# CH32H417MEU6-UHSIF-Bottom-R0.net
KiCad netlist of a schematic drawn in Altium Designer
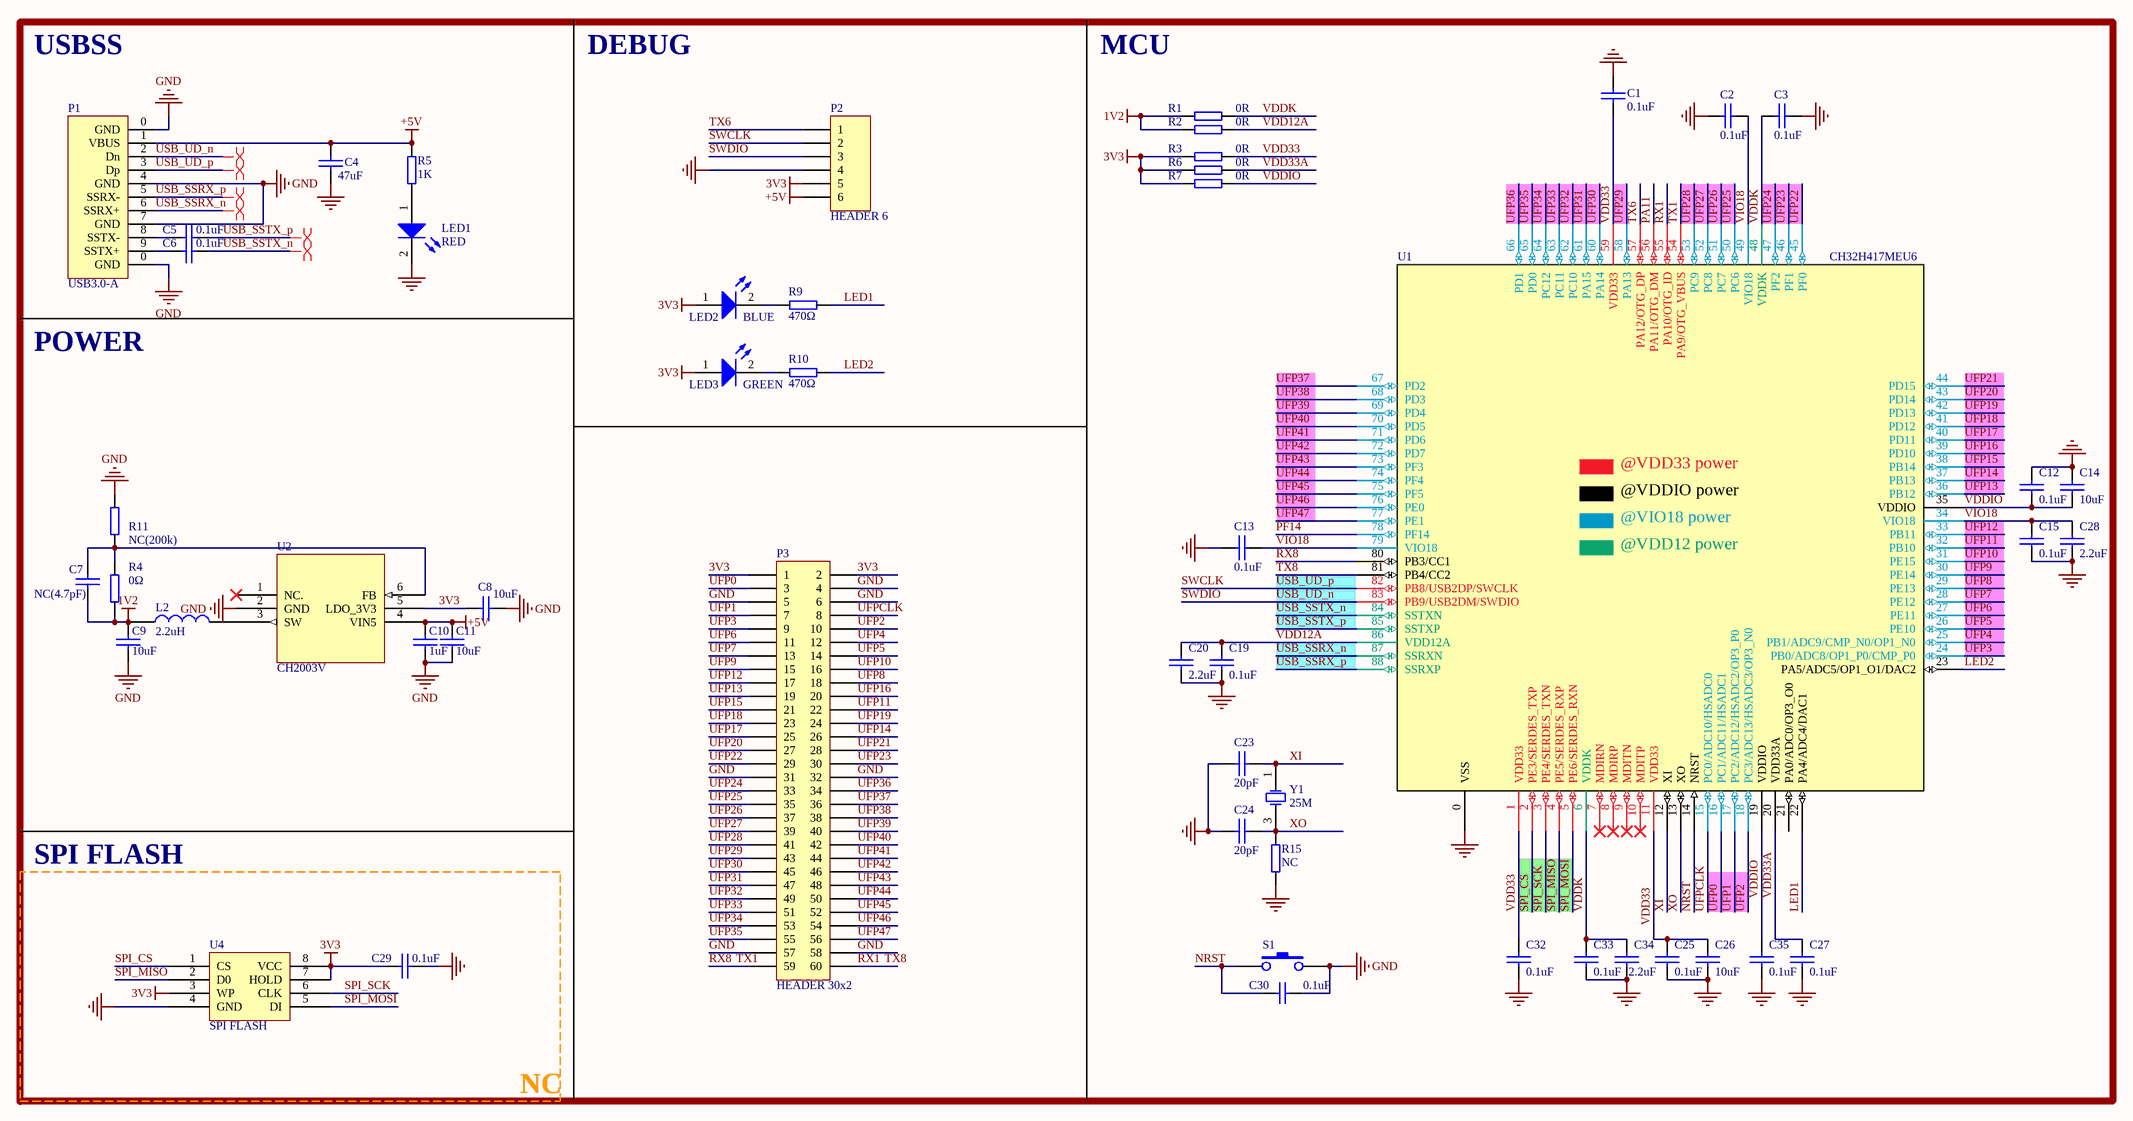
[diagram p0: CH32H417MEU6-UHSIF-Bottom-R0.SchDoc]

(export (version "E")
  (design (tool "Eeschema 10.0.6"))
  (components
    (comp (ref "C1")
      (value "0.1uF")
      (footprint "0402_C")
      (description "Capacitor")
      (libsource (lib "wch_sch_others") (part "CAP"))
    )
    (comp (ref "C2")
      (value "0.1uF")
      (footprint "0402_C")
      (description "Capacitor")
      (libsource (lib "wch_sch_others") (part "CAP"))
    )
    (comp (ref "C3")
      (value "0.1uF")
      (footprint "0402_C")
      (description "Capacitor")
      (libsource (lib "wch_sch_others") (part "CAP"))
    )
    (comp (ref "C4")
      (value "47uF")
      (footprint "3528_C")
      (description "Capacitor")
      (libsource (lib "wch_sch_others") (part "CAP"))
    )
    (comp (ref "C5")
      (value "0.1uF")
      (footprint "0402_C")
      (description "Capacitor")
      (libsource (lib "wch_sch_others") (part "CAP"))
    )
    (comp (ref "C6")
      (value "0.1uF")
      (footprint "0402_C")
      (description "Capacitor")
      (libsource (lib "wch_sch_others") (part "CAP"))
    )
    (comp (ref "C7")
      (value "NC(4.7pF)")
      (footprint "0402_C")
      (description "Capacitor")
      (libsource (lib "") (part "CAP_1"))
    )
    (comp (ref "C8")
      (value "10uF")
      (footprint "0603_C")
      (description "Capacitor")
      (libsource (lib "*") (part "CAP"))
    )
    (comp (ref "C9")
      (value "10uF")
      (footprint "0603_C")
      (description "Capacitor")
      (libsource (lib "*") (part "CAP"))
    )
    (comp (ref "C10")
      (value "1uF")
      (footprint "0402_C")
      (description "Capacitor")
      (libsource (lib "") (part "CAP_1"))
    )
    (comp (ref "C11")
      (value "10uF")
      (footprint "0603_C")
      (description "Capacitor")
      (libsource (lib "*") (part "CAP"))
    )
    (comp (ref "C12")
      (value "0.1uF")
      (footprint "0402_C")
      (description "Capacitor")
      (libsource (lib "wch_sch_others") (part "CAP"))
    )
    (comp (ref "C13")
      (value "0.1uF")
      (footprint "0402_C")
      (description "Capacitor")
      (libsource (lib "wch_sch_others") (part "CAP"))
    )
    (comp (ref "C14")
      (value "10uF")
      (footprint "0402_C")
      (description "Capacitor")
      (libsource (lib "wch_sch_others") (part "CAP"))
    )
    (comp (ref "C15")
      (value "0.1uF")
      (footprint "0402_C")
      (description "Capacitor")
      (libsource (lib "wch_sch_others") (part "CAP"))
    )
    (comp (ref "C19")
      (value "0.1uF")
      (footprint "0402_C")
      (description "Capacitor")
      (libsource (lib "wch_sch_others") (part "CAP"))
    )
    (comp (ref "C20")
      (value "2.2uF")
      (footprint "0402_C")
      (description "Capacitor")
      (libsource (lib "wch_sch_others") (part "CAP"))
    )
    (comp (ref "C23")
      (value "20pF")
      (footprint "0402_C")
      (description "Capacitor")
      (libsource (lib "wch_sch_others") (part "CAP"))
    )
    (comp (ref "C24")
      (value "20pF")
      (footprint "0402_C")
      (description "Capacitor")
      (libsource (lib "wch_sch_others") (part "CAP"))
    )
    (comp (ref "C25")
      (value "0.1uF")
      (footprint "0402_C")
      (description "Capacitor")
      (libsource (lib "wch_sch_others") (part "CAP"))
    )
    (comp (ref "C26")
      (value "10uF")
      (footprint "0402_C")
      (description "Capacitor")
      (libsource (lib "wch_sch_others") (part "CAP"))
    )
    (comp (ref "C27")
      (value "0.1uF")
      (footprint "0402_C")
      (description "Capacitor")
      (libsource (lib "wch_sch_others") (part "CAP"))
    )
    (comp (ref "C28")
      (value "2.2uF")
      (footprint "0402_C")
      (description "Capacitor")
      (libsource (lib "wch_sch_others") (part "CAP"))
    )
    (comp (ref "C29")
      (value "0.1uF")
      (footprint "0402_C")
      (description "Capacitor")
      (libsource (lib "wch_sch_others") (part "CAP"))
    )
    (comp (ref "C30")
      (value "0.1uF")
      (footprint "0402_C")
      (description "Capacitor")
      (libsource (lib "Miscellaneous Devices") (part "Cap"))
    )
    (comp (ref "C32")
      (value "0.1uF")
      (footprint "0402_C")
      (description "Capacitor")
      (libsource (lib "wch_sch_others") (part "CAP"))
    )
    (comp (ref "C33")
      (value "0.1uF")
      (footprint "0402_C")
      (description "Capacitor")
      (libsource (lib "wch_sch_others") (part "CAP"))
    )
    (comp (ref "C34")
      (value "2.2uF")
      (footprint "0402_C")
      (description "Capacitor")
      (libsource (lib "wch_sch_others") (part "CAP"))
    )
    (comp (ref "C35")
      (value "0.1uF")
      (footprint "0402_C")
      (description "Capacitor")
      (libsource (lib "wch_sch_others") (part "CAP"))
    )
    (comp (ref "L2") (value "2.2uH") (footprint "CD32") (libsource (lib "*") (part "INDUCTOR")))
    (comp (ref "LED1")
      (value "RED")
      (footprint "MYPCB:0603+")
      (description "Typical INFRARED GaAs LED")
      (libsource (lib "wch_sch_others") (part "LED"))
    )
    (comp (ref "LED2")
      (value "BLUE")
      (footprint "MYPCB:0603+")
      (description "Typical INFRARED GaAs LED")
      (libsource (lib "wch_sch_others") (part "LED"))
    )
    (comp (ref "LED3")
      (value "GREEN")
      (footprint "MYPCB:0603+")
      (description "Typical INFRARED GaAs LED")
      (libsource (lib "wch_sch_others") (part "LED"))
    )
    (comp (ref "P1")
      (value "USB3.0-A")
      (footprint "USB3.0-A-Receptacle")
      (libsource (lib "wch_sch_others") (part "USB3.0-A"))
    )
    (comp (ref "P2")
      (value "HEADER 6")
      (footprint "SIP6-2.54mm")
      (description "Header, 6-Pin")
      (libsource (lib "wch_sch_others") (part "HEADER 6"))
    )
    (comp (ref "P3")
      (value "HEADER 30x2")
      (footprint "MYPCB:BTB-60P-P0.5-MR")
      (description "Header, 30-Pin, Dual row")
      (libsource (lib "wch_sch_others") (part "HEADER 30x2"))
    )
    (comp (ref "R1") (value "0R") (footprint "0603") (libsource (lib "wch_sch_others") (part "RES")))
    (comp (ref "R2") (value "0R") (footprint "0603") (libsource (lib "wch_sch_others") (part "RES")))
    (comp (ref "R3") (value "0R") (footprint "0603") (libsource (lib "wch_sch_others") (part "RES")))
    (comp (ref "R4") (value "0Ω") (footprint "0402") (libsource (lib "wch_sch_others") (part "RES")))
    (comp (ref "R5") (value "1K") (footprint "0402") (libsource (lib "wch_sch_others") (part "RES")))
    (comp (ref "R6") (value "0R") (footprint "0603") (libsource (lib "wch_sch_others") (part "RES")))
    (comp (ref "R7") (value "0R") (footprint "0603") (libsource (lib "wch_sch_others") (part "RES")))
    (comp (ref "R9") (value "470Ω") (footprint "0402") (libsource (lib "wch_sch_others") (part "RES")))
    (comp (ref "R10") (value "470Ω") (footprint "0402") (libsource (lib "wch_sch_others") (part "RES")))
    (comp (ref "R11") (value "NC(200k)") (footprint "0402") (libsource (lib "wch_sch_others") (part "RES")))
    (comp (ref "R15") (value "NC") (footprint "0402") (libsource (lib "*") (part "RES")))
    (comp (ref "S1") (value "~") (footprint "贴片按键") (libsource (lib "wch_sch_others") (part "KEY1")))
    (comp (ref "U1")
      (value "CH32H417MEU6")
      (footprint "QFN88_10X10")
      (description "RISC-V FPU HD-MCU, 384MHz, USB3.0 & PD, 100M Ethernet, DVP, SDMMC, QSPI, OPA, ADC, DAC")
      (libsource (lib "DHXXXSCH") (part "CH32H417MEU6"))
    )
    (comp (ref "U2")
      (value "CH2003V")
      (footprint "SOT-23-6")
      (description "Step-Down DC-DC Converter, 5V input, FB 0.6V, 800mA output, with LDO 3.3V * 200mA")
      (libsource (lib "DHXXXSCH") (part "CH2003K"))
    )
    (comp (ref "U4")
      (value "SPI FLASH")
      (footprint "SOIC-8_208mil")
      (libsource (lib "wch_sch_others") (part "W25Q64"))
    )
    (comp (ref "Y1")
      (value "25M")
      (footprint "XT3225")
      (description "Crystal Oscillator")
      (fields (field (name "PUBLISHER") "Altium Limited"))
      (libsource (lib "Miscellaneous Devices") (part "XTAL"))
    )
  )
  (nets
    (net (code "1") (name "+5V") (class "Default")
      (node (ref "C10") (pin "2") (pinfunction "2_2") (pintype "passive"))
      (node (ref "C11") (pin "2") (pinfunction "2_2") (pintype "passive"))
      (node (ref "C4") (pin "1") (pinfunction "1_1") (pintype "passive"))
      (node (ref "P1") (pin "1") (pinfunction "VBUS_1") (pintype "passive"))
      (node (ref "P2") (pin "6") (pinfunction "6_6") (pintype "passive"))
      (node (ref "R5") (pin "2") (pintype "passive"))
      (node (ref "U2") (pin "4") (pinfunction "VIN5_4") (pintype "power_in"))
    )
    (net (code "2") (name "/LED1") (class "Default")
      (node (ref "R9") (pin "1") (pintype "passive"))
      (node (ref "U1") (pin "22") (pinfunction "PA4/ADC4/DAC1_22") (pintype "bidirectional"))
    )
    (net (code "3") (name "/LED2") (class "Default")
      (node (ref "R10") (pin "1") (pintype "passive"))
      (node (ref "U1") (pin "23") (pinfunction "PA5/ADC5/OP1_O1/DAC2_23") (pintype "bidirectional"))
    )
    (net (code "4") (name "/NRST") (class "Default")
      (node (ref "C30") (pin "2") (pinfunction "2_2") (pintype "passive"))
      (node (ref "S1") (pin "1") (pinfunction "1_1") (pintype "passive"))
      (node (ref "U1") (pin "14") (pinfunction "NRST_14") (pintype "input"))
    )
    (net (code "5") (name "/PA11") (class "Default")
      (node (ref "U1") (pin "56") (pinfunction "PA11/OTG_DM_56") (pintype "bidirectional"))
    )
    (net (code "6") (name "/PF14") (class "Default")
      (node (ref "U1") (pin "78") (pinfunction "PF14_78") (pintype "bidirectional"))
    )
    (net (code "7") (name "/RX1") (class "Default")
      (node (ref "P3") (pin "60") (pinfunction "60_60") (pintype "passive"))
      (node (ref "U1") (pin "55") (pinfunction "PA10/OTG_ID_55") (pintype "bidirectional"))
      (node (ref "U1") (pin "81") (pinfunction "PB4/CC2_81") (pintype "bidirectional"))
    )
    (net (code "8") (name "/RX8") (class "Default")
      (node (ref "P3") (pin "59") (pinfunction "59_59") (pintype "passive"))
      (node (ref "U1") (pin "54") (pinfunction "PA9/OTG_VBUS_54") (pintype "bidirectional"))
      (node (ref "U1") (pin "80") (pinfunction "PB3/CC1_80") (pintype "bidirectional"))
    )
    (net (code "9") (name "/SPI_CS") (class "Default")
      (node (ref "U1") (pin "2") (pinfunction "PE3/SERDES_TXP_2") (pintype "bidirectional"))
      (node (ref "U4") (pin "1") (pinfunction "CS_1") (pintype "passive"))
    )
    (net (code "10") (name "/SPI_MISO") (class "Default")
      (node (ref "U1") (pin "4") (pinfunction "PE5/SERDES_RXP_4") (pintype "bidirectional"))
      (node (ref "U4") (pin "2") (pinfunction "D0_2") (pintype "passive"))
    )
    (net (code "11") (name "/SPI_MOSI") (class "Default")
      (node (ref "U1") (pin "5") (pinfunction "PE6/SERDES_RXN_5") (pintype "bidirectional"))
      (node (ref "U4") (pin "5") (pinfunction "DI_5") (pintype "passive"))
    )
    (net (code "12") (name "/SPI_SCK") (class "Default")
      (node (ref "U1") (pin "3") (pinfunction "PE4/SERDES_TXN_3") (pintype "bidirectional"))
      (node (ref "U4") (pin "6") (pinfunction "CLK_6") (pintype "passive"))
    )
    (net (code "13") (name "/SWCLK") (class "Default")
      (node (ref "P1") (pin "3") (pinfunction "Dp_3") (pintype "passive"))
      (node (ref "P2") (pin "2") (pinfunction "2_2") (pintype "passive"))
      (node (ref "U1") (pin "82") (pinfunction "PB8/USB2DP/SWCLK_82") (pintype "bidirectional"))
    )
    (net (code "14") (name "/SWDIO") (class "Default")
      (node (ref "P1") (pin "2") (pinfunction "Dn_2") (pintype "passive"))
      (node (ref "P2") (pin "3") (pinfunction "3_3") (pintype "passive"))
      (node (ref "U1") (pin "83") (pinfunction "PB9/USB2DM/SWDIO_83") (pintype "bidirectional"))
    )
    (net (code "15") (name "/TX6") (class "Default")
      (node (ref "P2") (pin "1") (pinfunction "1_1") (pintype "passive"))
      (node (ref "U1") (pin "57") (pinfunction "PA12/OTG_DP_57") (pintype "bidirectional"))
    )
    (net (code "16") (name "/UFP0") (class "Default")
      (node (ref "P3") (pin "3") (pinfunction "3_3") (pintype "passive"))
      (node (ref "U1") (pin "16") (pinfunction "PC1/ADC11/HSADC1_16") (pintype "bidirectional"))
    )
    (net (code "17") (name "/UFP1") (class "Default")
      (node (ref "P3") (pin "7") (pinfunction "7_7") (pintype "passive"))
      (node (ref "U1") (pin "17") (pinfunction "PC2/ADC12/HSADC2/OP3_P0_17") (pintype "bidirectional"))
    )
    (net (code "18") (name "/UFP2") (class "Default")
      (node (ref "P3") (pin "10") (pinfunction "10_10") (pintype "passive"))
      (node (ref "U1") (pin "18") (pinfunction "PC3/ADC13/HSADC3/OP3_N0_18") (pintype "bidirectional"))
    )
    (net (code "19") (name "/UFP3") (class "Default")
      (node (ref "P3") (pin "9") (pinfunction "9_9") (pintype "passive"))
      (node (ref "U1") (pin "24") (pinfunction "PB0/ADC8/OP1_P0/CMP_P0_24") (pintype "bidirectional"))
    )
    (net (code "20") (name "/UFP4") (class "Default")
      (node (ref "P3") (pin "12") (pinfunction "12_12") (pintype "passive"))
      (node (ref "U1") (pin "25") (pinfunction "PB1/ADC9/CMP_N0/OP1_N0_25") (pintype "bidirectional"))
    )
    (net (code "21") (name "/UFP5") (class "Default")
      (node (ref "P3") (pin "14") (pinfunction "14_14") (pintype "passive"))
      (node (ref "U1") (pin "26") (pinfunction "PE10_26") (pintype "bidirectional"))
    )
    (net (code "22") (name "/UFP6") (class "Default")
      (node (ref "P3") (pin "11") (pinfunction "11_11") (pintype "passive"))
      (node (ref "U1") (pin "27") (pinfunction "PE11_27") (pintype "bidirectional"))
    )
    (net (code "23") (name "/UFP7") (class "Default")
      (node (ref "P3") (pin "13") (pinfunction "13_13") (pintype "passive"))
      (node (ref "U1") (pin "28") (pinfunction "PE12_28") (pintype "bidirectional"))
    )
    (net (code "24") (name "/UFP8") (class "Default")
      (node (ref "P3") (pin "18") (pinfunction "18_18") (pintype "passive"))
      (node (ref "U1") (pin "29") (pinfunction "PE13_29") (pintype "bidirectional"))
    )
    (net (code "25") (name "/UFP9") (class "Default")
      (node (ref "P3") (pin "15") (pinfunction "15_15") (pintype "passive"))
      (node (ref "U1") (pin "30") (pinfunction "PE14_30") (pintype "bidirectional"))
    )
    (net (code "26") (name "/UFP10") (class "Default")
      (node (ref "P3") (pin "16") (pinfunction "16_16") (pintype "passive"))
      (node (ref "U1") (pin "31") (pinfunction "PE15_31") (pintype "bidirectional"))
    )
    (net (code "27") (name "/UFP11") (class "Default")
      (node (ref "P3") (pin "22") (pinfunction "22_22") (pintype "passive"))
      (node (ref "U1") (pin "32") (pinfunction "PB10_32") (pintype "bidirectional"))
    )
    (net (code "28") (name "/UFP12") (class "Default")
      (node (ref "P3") (pin "17") (pinfunction "17_17") (pintype "passive"))
      (node (ref "U1") (pin "33") (pinfunction "PB11_33") (pintype "bidirectional"))
    )
    (net (code "29") (name "/UFP13") (class "Default")
      (node (ref "P3") (pin "19") (pinfunction "19_19") (pintype "passive"))
      (node (ref "U1") (pin "36") (pinfunction "PB12_36") (pintype "bidirectional"))
    )
    (net (code "30") (name "/UFP14") (class "Default")
      (node (ref "P3") (pin "26") (pinfunction "26_26") (pintype "passive"))
      (node (ref "U1") (pin "37") (pinfunction "PB13_37") (pintype "bidirectional"))
    )
    (net (code "31") (name "/UFP15") (class "Default")
      (node (ref "P3") (pin "21") (pinfunction "21_21") (pintype "passive"))
      (node (ref "U1") (pin "38") (pinfunction "PB14_38") (pintype "bidirectional"))
    )
    (net (code "32") (name "/UFP16") (class "Default")
      (node (ref "P3") (pin "20") (pinfunction "20_20") (pintype "passive"))
      (node (ref "U1") (pin "39") (pinfunction "PD10_39") (pintype "bidirectional"))
    )
    (net (code "33") (name "/UFP17") (class "Default")
      (node (ref "P3") (pin "25") (pinfunction "25_25") (pintype "passive"))
      (node (ref "U1") (pin "40") (pinfunction "PD11_40") (pintype "bidirectional"))
    )
    (net (code "34") (name "/UFP18") (class "Default")
      (node (ref "P3") (pin "23") (pinfunction "23_23") (pintype "passive"))
      (node (ref "U1") (pin "41") (pinfunction "PD12_41") (pintype "bidirectional"))
    )
    (net (code "35") (name "/UFP19") (class "Default")
      (node (ref "P3") (pin "24") (pinfunction "24_24") (pintype "passive"))
      (node (ref "U1") (pin "42") (pinfunction "PD13_42") (pintype "bidirectional"))
    )
    (net (code "36") (name "/UFP20") (class "Default")
      (node (ref "P3") (pin "27") (pinfunction "27_27") (pintype "passive"))
      (node (ref "U1") (pin "43") (pinfunction "PD14_43") (pintype "bidirectional"))
    )
    (net (code "37") (name "/UFP21") (class "Default")
      (node (ref "P3") (pin "28") (pinfunction "28_28") (pintype "passive"))
      (node (ref "U1") (pin "44") (pinfunction "PD15_44") (pintype "bidirectional"))
    )
    (net (code "38") (name "/UFP22") (class "Default")
      (node (ref "P3") (pin "29") (pinfunction "29_29") (pintype "passive"))
      (node (ref "U1") (pin "45") (pinfunction "PF0_45") (pintype "bidirectional"))
    )
    (net (code "39") (name "/UFP23") (class "Default")
      (node (ref "P3") (pin "30") (pinfunction "30_30") (pintype "passive"))
      (node (ref "U1") (pin "46") (pinfunction "PF1_46") (pintype "bidirectional"))
    )
    (net (code "40") (name "/UFP24") (class "Default")
      (node (ref "P3") (pin "33") (pinfunction "33_33") (pintype "passive"))
      (node (ref "U1") (pin "47") (pinfunction "PF2_47") (pintype "bidirectional"))
    )
    (net (code "41") (name "/UFP25") (class "Default")
      (node (ref "P3") (pin "35") (pinfunction "35_35") (pintype "passive"))
      (node (ref "U1") (pin "50") (pinfunction "PC6_50") (pintype "bidirectional"))
    )
    (net (code "42") (name "/UFP26") (class "Default")
      (node (ref "P3") (pin "37") (pinfunction "37_37") (pintype "passive"))
      (node (ref "U1") (pin "51") (pinfunction "PC7_51") (pintype "bidirectional"))
    )
    (net (code "43") (name "/UFP27") (class "Default")
      (node (ref "P3") (pin "39") (pinfunction "39_39") (pintype "passive"))
      (node (ref "U1") (pin "52") (pinfunction "PC8_52") (pintype "bidirectional"))
    )
    (net (code "44") (name "/UFP28") (class "Default")
      (node (ref "P3") (pin "41") (pinfunction "41_41") (pintype "passive"))
      (node (ref "U1") (pin "53") (pinfunction "PC9_53") (pintype "bidirectional"))
    )
    (net (code "45") (name "/UFP29") (class "Default")
      (node (ref "P3") (pin "43") (pinfunction "43_43") (pintype "passive"))
      (node (ref "U1") (pin "58") (pinfunction "PA13_58") (pintype "bidirectional"))
    )
    (net (code "46") (name "/UFP30") (class "Default")
      (node (ref "P3") (pin "45") (pinfunction "45_45") (pintype "passive"))
      (node (ref "U1") (pin "60") (pinfunction "PA14_60") (pintype "bidirectional"))
    )
    (net (code "47") (name "/UFP31") (class "Default")
      (node (ref "P3") (pin "47") (pinfunction "47_47") (pintype "passive"))
      (node (ref "U1") (pin "61") (pinfunction "PA15_61") (pintype "bidirectional"))
    )
    (net (code "48") (name "/UFP32") (class "Default")
      (node (ref "P3") (pin "49") (pinfunction "49_49") (pintype "passive"))
      (node (ref "U1") (pin "62") (pinfunction "PC10_62") (pintype "bidirectional"))
    )
    (net (code "49") (name "/UFP33") (class "Default")
      (node (ref "P3") (pin "51") (pinfunction "51_51") (pintype "passive"))
      (node (ref "U1") (pin "63") (pinfunction "PC11_63") (pintype "bidirectional"))
    )
    (net (code "50") (name "/UFP34") (class "Default")
      (node (ref "P3") (pin "53") (pinfunction "53_53") (pintype "passive"))
      (node (ref "U1") (pin "64") (pinfunction "PC12_64") (pintype "bidirectional"))
    )
    (net (code "51") (name "/UFP35") (class "Default")
      (node (ref "P3") (pin "55") (pinfunction "55_55") (pintype "passive"))
      (node (ref "U1") (pin "65") (pinfunction "PD0_65") (pintype "bidirectional"))
    )
    (net (code "52") (name "/UFP36") (class "Default")
      (node (ref "P3") (pin "34") (pinfunction "34_34") (pintype "passive"))
      (node (ref "U1") (pin "66") (pinfunction "PD1_66") (pintype "bidirectional"))
    )
    (net (code "53") (name "/UFP37") (class "Default")
      (node (ref "P3") (pin "36") (pinfunction "36_36") (pintype "passive"))
      (node (ref "U1") (pin "67") (pinfunction "PD2_67") (pintype "bidirectional"))
    )
    (net (code "54") (name "/UFP38") (class "Default")
      (node (ref "P3") (pin "38") (pinfunction "38_38") (pintype "passive"))
      (node (ref "U1") (pin "68") (pinfunction "PD3_68") (pintype "bidirectional"))
    )
    (net (code "55") (name "/UFP39") (class "Default")
      (node (ref "P3") (pin "40") (pinfunction "40_40") (pintype "passive"))
      (node (ref "U1") (pin "69") (pinfunction "PD4_69") (pintype "bidirectional"))
    )
    (net (code "56") (name "/UFP40") (class "Default")
      (node (ref "P3") (pin "42") (pinfunction "42_42") (pintype "passive"))
      (node (ref "U1") (pin "70") (pinfunction "PD5_70") (pintype "bidirectional"))
    )
    (net (code "57") (name "/UFP41") (class "Default")
      (node (ref "P3") (pin "44") (pinfunction "44_44") (pintype "passive"))
      (node (ref "U1") (pin "71") (pinfunction "PD6_71") (pintype "bidirectional"))
    )
    (net (code "58") (name "/UFP42") (class "Default")
      (node (ref "P3") (pin "46") (pinfunction "46_46") (pintype "passive"))
      (node (ref "U1") (pin "72") (pinfunction "PD7_72") (pintype "bidirectional"))
    )
    (net (code "59") (name "/UFP43") (class "Default")
      (node (ref "P3") (pin "48") (pinfunction "48_48") (pintype "passive"))
      (node (ref "U1") (pin "73") (pinfunction "PF3_73") (pintype "bidirectional"))
    )
    (net (code "60") (name "/UFP44") (class "Default")
      (node (ref "P3") (pin "50") (pinfunction "50_50") (pintype "passive"))
      (node (ref "U1") (pin "74") (pinfunction "PF4_74") (pintype "bidirectional"))
    )
    (net (code "61") (name "/UFP45") (class "Default")
      (node (ref "P3") (pin "52") (pinfunction "52_52") (pintype "passive"))
      (node (ref "U1") (pin "75") (pinfunction "PF5_75") (pintype "bidirectional"))
    )
    (net (code "62") (name "/UFP46") (class "Default")
      (node (ref "P3") (pin "54") (pinfunction "54_54") (pintype "passive"))
      (node (ref "U1") (pin "76") (pinfunction "PE0_76") (pintype "bidirectional"))
    )
    (net (code "63") (name "/UFP47") (class "Default")
      (node (ref "P3") (pin "56") (pinfunction "56_56") (pintype "passive"))
      (node (ref "U1") (pin "77") (pinfunction "PE1_77") (pintype "bidirectional"))
    )
    (net (code "64") (name "/UFPCLK") (class "Default")
      (node (ref "P3") (pin "8") (pinfunction "8_8") (pintype "passive"))
      (node (ref "U1") (pin "15") (pinfunction "PC0/ADC10/HSADC0_15") (pintype "bidirectional"))
    )
    (net (code "65") (name "/USB_SSRX_n") (class "Default")
      (node (ref "P1") (pin "6") (pinfunction "SSRX+_6") (pintype "passive"))
      (node (ref "U1") (pin "87") (pinfunction "SSRXN_87") (pintype "bidirectional"))
    )
    (net (code "66") (name "/USB_SSRX_p") (class "Default")
      (node (ref "P1") (pin "5") (pinfunction "SSRX-_5") (pintype "passive"))
      (node (ref "U1") (pin "88") (pinfunction "SSRXP_88") (pintype "bidirectional"))
    )
    (net (code "67") (name "/USB_SSTX_n") (class "Default")
      (node (ref "C6") (pin "1") (pinfunction "1_1") (pintype "passive"))
      (node (ref "U1") (pin "84") (pinfunction "SSTXN_84") (pintype "bidirectional"))
    )
    (net (code "68") (name "/USB_SSTX_p") (class "Default")
      (node (ref "C5") (pin "1") (pinfunction "1_1") (pintype "passive"))
      (node (ref "U1") (pin "85") (pinfunction "SSTXP_85") (pintype "bidirectional"))
    )
    (net (code "69") (name "/VDD12A") (class "Default")
      (node (ref "C19") (pin "2") (pinfunction "2_2") (pintype "passive"))
      (node (ref "C20") (pin "2") (pinfunction "2_2") (pintype "passive"))
      (node (ref "R2") (pin "1") (pintype "passive"))
      (node (ref "U1") (pin "86") (pinfunction "VDD12A_86") (pintype "power_in"))
    )
    (net (code "70") (name "/VDD33") (class "Default")
      (node (ref "C1") (pin "1") (pinfunction "1_1") (pintype "passive"))
      (node (ref "C25") (pin "2") (pinfunction "2_2") (pintype "passive"))
      (node (ref "C26") (pin "2") (pinfunction "2_2") (pintype "passive"))
      (node (ref "C32") (pin "2") (pinfunction "2_2") (pintype "passive"))
      (node (ref "R3") (pin "1") (pintype "passive"))
      (node (ref "U1") (pin "1") (pinfunction "VDD33_1") (pintype "power_in"))
      (node (ref "U1") (pin "11") (pinfunction "VDD33_11") (pintype "power_in"))
      (node (ref "U1") (pin "59") (pinfunction "VDD33_59") (pintype "power_in"))
    )
    (net (code "71") (name "/VDD33A") (class "Default")
      (node (ref "C27") (pin "2") (pinfunction "2_2") (pintype "passive"))
      (node (ref "R6") (pin "1") (pintype "passive"))
      (node (ref "U1") (pin "20") (pinfunction "VDD33A_20") (pintype "power_in"))
    )
    (net (code "72") (name "/VDDIO") (class "Default")
      (node (ref "C12") (pin "1") (pinfunction "1_1") (pintype "passive"))
      (node (ref "C14") (pin "1") (pinfunction "1_1") (pintype "passive"))
      (node (ref "C35") (pin "2") (pinfunction "2_2") (pintype "passive"))
      (node (ref "R7") (pin "1") (pintype "passive"))
      (node (ref "U1") (pin "19") (pinfunction "VDDIO_19") (pintype "power_in"))
      (node (ref "U1") (pin "35") (pinfunction "VDDIO_35") (pintype "power_in"))
    )
    (net (code "73") (name "/VDDK") (class "Default")
      (node (ref "C3") (pin "2") (pinfunction "2_2") (pintype "passive"))
      (node (ref "C33") (pin "2") (pinfunction "2_2") (pintype "passive"))
      (node (ref "C34") (pin "2") (pinfunction "2_2") (pintype "passive"))
      (node (ref "R1") (pin "1") (pintype "passive"))
      (node (ref "U1") (pin "48") (pinfunction "VDDK_48") (pintype "power_in"))
      (node (ref "U1") (pin "6") (pinfunction "VDDK_6") (pintype "power_in"))
    )
    (net (code "74") (name "/VIO18") (class "Default")
      (node (ref "C13") (pin "1") (pinfunction "1_1") (pintype "passive"))
      (node (ref "C15") (pin "2") (pinfunction "2_2") (pintype "passive"))
      (node (ref "C2") (pin "1") (pinfunction "1_1") (pintype "passive"))
      (node (ref "C28") (pin "2") (pinfunction "2_2") (pintype "passive"))
      (node (ref "U1") (pin "34") (pinfunction "VIO18_34") (pintype "power_in"))
      (node (ref "U1") (pin "49") (pinfunction "VIO18_49") (pintype "power_in"))
      (node (ref "U1") (pin "79") (pinfunction "VIO18_79") (pintype "power_in"))
    )
    (net (code "75") (name "/XI") (class "Default")
      (node (ref "C23") (pin "2") (pinfunction "2_2") (pintype "passive"))
      (node (ref "U1") (pin "12") (pinfunction "XI_12") (pintype "bidirectional"))
      (node (ref "Y1") (pin "1") (pinfunction "OSC1_1") (pintype "passive"))
    )
    (net (code "76") (name "/XO") (class "Default")
      (node (ref "C24") (pin "2") (pinfunction "2_2") (pintype "passive"))
      (node (ref "R15") (pin "2") (pintype "passive"))
      (node (ref "U1") (pin "13") (pinfunction "XO_13") (pintype "bidirectional"))
      (node (ref "Y1") (pin "3") (pinfunction "OSC2_3") (pintype "passive"))
    )
    (net (code "77") (name "1V2") (class "Default")
      (node (ref "C7") (pin "1") (pinfunction "1_1") (pintype "passive"))
      (node (ref "C9") (pin "2") (pinfunction "2_2") (pintype "passive"))
      (node (ref "L2") (pin "2") (pinfunction "2_2") (pintype "passive"))
      (node (ref "R1") (pin "2") (pintype "passive"))
      (node (ref "R2") (pin "2") (pintype "passive"))
      (node (ref "R4") (pin "1") (pintype "passive"))
    )
    (net (code "78") (name "3V3") (class "Default")
      (node (ref "C29") (pin "2") (pinfunction "2_2") (pintype "passive"))
      (node (ref "C8") (pin "2") (pinfunction "2_2") (pintype "passive"))
      (node (ref "LED2") (pin "1") (pinfunction "A_1") (pintype "passive"))
      (node (ref "LED3") (pin "1") (pinfunction "A_1") (pintype "passive"))
      (node (ref "P2") (pin "5") (pinfunction "5_5") (pintype "passive"))
      (node (ref "P3") (pin "1") (pinfunction "1_1") (pintype "passive"))
      (node (ref "P3") (pin "2") (pinfunction "2_2") (pintype "passive"))
      (node (ref "R3") (pin "2") (pintype "passive"))
      (node (ref "R6") (pin "2") (pintype "passive"))
      (node (ref "R7") (pin "2") (pintype "passive"))
      (node (ref "U2") (pin "5") (pinfunction "LDO_3V3_5") (pintype "power_in"))
      (node (ref "U4") (pin "3") (pinfunction "WP_3") (pintype "passive"))
      (node (ref "U4") (pin "7") (pinfunction "HOLD_7") (pintype "passive"))
      (node (ref "U4") (pin "8") (pinfunction "VCC_8") (pintype "passive"))
    )
    (net (code "79") (name "GND") (class "Default")
      (node (ref "C1") (pin "2") (pinfunction "2_2") (pintype "passive"))
      (node (ref "C10") (pin "1") (pinfunction "1_1") (pintype "passive"))
      (node (ref "C11") (pin "1") (pinfunction "1_1") (pintype "passive"))
      (node (ref "C12") (pin "2") (pinfunction "2_2") (pintype "passive"))
      (node (ref "C13") (pin "2") (pinfunction "2_2") (pintype "passive"))
      (node (ref "C14") (pin "2") (pinfunction "2_2") (pintype "passive"))
      (node (ref "C15") (pin "1") (pinfunction "1_1") (pintype "passive"))
      (node (ref "C19") (pin "1") (pinfunction "1_1") (pintype "passive"))
      (node (ref "C2") (pin "2") (pinfunction "2_2") (pintype "passive"))
      (node (ref "C20") (pin "1") (pinfunction "1_1") (pintype "passive"))
      (node (ref "C23") (pin "1") (pinfunction "1_1") (pintype "passive"))
      (node (ref "C24") (pin "1") (pinfunction "1_1") (pintype "passive"))
      (node (ref "C25") (pin "1") (pinfunction "1_1") (pintype "passive"))
      (node (ref "C26") (pin "1") (pinfunction "1_1") (pintype "passive"))
      (node (ref "C27") (pin "1") (pinfunction "1_1") (pintype "passive"))
      (node (ref "C28") (pin "1") (pinfunction "1_1") (pintype "passive"))
      (node (ref "C29") (pin "1") (pinfunction "1_1") (pintype "passive"))
      (node (ref "C3") (pin "1") (pinfunction "1_1") (pintype "passive"))
      (node (ref "C30") (pin "1") (pinfunction "1_1") (pintype "passive"))
      (node (ref "C32") (pin "1") (pinfunction "1_1") (pintype "passive"))
      (node (ref "C33") (pin "1") (pinfunction "1_1") (pintype "passive"))
      (node (ref "C34") (pin "1") (pinfunction "1_1") (pintype "passive"))
      (node (ref "C35") (pin "1") (pinfunction "1_1") (pintype "passive"))
      (node (ref "C4") (pin "2") (pinfunction "2_2") (pintype "passive"))
      (node (ref "C8") (pin "1") (pinfunction "1_1") (pintype "passive"))
      (node (ref "C9") (pin "1") (pinfunction "1_1") (pintype "passive"))
      (node (ref "LED1") (pin "2") (pinfunction "K_2") (pintype "passive"))
      (node (ref "P1") (pin "0") (pinfunction "GND_0") (pintype "passive"))
      (node (ref "P1") (pin "4") (pinfunction "GND_4") (pintype "passive"))
      (node (ref "P1") (pin "7") (pinfunction "GND_7") (pintype "passive"))
      (node (ref "P2") (pin "4") (pinfunction "4_4") (pintype "passive"))
      (node (ref "P3") (pin "31") (pinfunction "31_31") (pintype "passive"))
      (node (ref "P3") (pin "32") (pinfunction "32_32") (pintype "passive"))
      (node (ref "P3") (pin "4") (pinfunction "4_4") (pintype "passive"))
      (node (ref "P3") (pin "5") (pinfunction "5_5") (pintype "passive"))
      (node (ref "P3") (pin "57") (pinfunction "57_57") (pintype "passive"))
      (node (ref "P3") (pin "58") (pinfunction "58_58") (pintype "passive"))
      (node (ref "P3") (pin "6") (pinfunction "6_6") (pintype "passive"))
      (node (ref "R11") (pin "2") (pintype "passive"))
      (node (ref "R15") (pin "1") (pintype "passive"))
      (node (ref "S1") (pin "2") (pinfunction "2_2") (pintype "passive"))
      (node (ref "U1") (pin "0") (pinfunction "VSS_0") (pintype "power_in"))
      (node (ref "U2") (pin "2") (pinfunction "GND_2") (pintype "power_in"))
      (node (ref "U4") (pin "4") (pinfunction "GND_4") (pintype "passive"))
    )
    (net (code "80") (name "Net-(LED1-A)") (class "Default")
      (node (ref "LED1") (pin "1") (pinfunction "A_1") (pintype "passive"))
      (node (ref "R5") (pin "1") (pintype "passive"))
    )
    (net (code "81") (name "Net-(LED2-K)") (class "Default")
      (node (ref "LED2") (pin "2") (pinfunction "K_2") (pintype "passive"))
      (node (ref "R9") (pin "2") (pintype "passive"))
    )
    (net (code "82") (name "Net-(LED3-K)") (class "Default")
      (node (ref "LED3") (pin "2") (pinfunction "K_2") (pintype "passive"))
      (node (ref "R10") (pin "2") (pintype "passive"))
    )
    (net (code "83") (name "Net-(P1-SSTX+)") (class "Default")
      (node (ref "C6") (pin "2") (pinfunction "2_2") (pintype "passive"))
      (node (ref "P1") (pin "9") (pinfunction "SSTX+_9") (pintype "passive"))
    )
    (net (code "84") (name "Net-(P1-SSTX-)") (class "Default")
      (node (ref "C5") (pin "2") (pinfunction "2_2") (pintype "passive"))
      (node (ref "P1") (pin "8") (pinfunction "SSTX-_8") (pintype "passive"))
    )
    (net (code "85") (name "Net-(U2-FB)") (class "Default")
      (node (ref "C7") (pin "2") (pinfunction "2_2") (pintype "passive"))
      (node (ref "R11") (pin "1") (pintype "passive"))
      (node (ref "R4") (pin "2") (pintype "passive"))
      (node (ref "U2") (pin "6") (pinfunction "FB_6") (pintype "input"))
    )
    (net (code "86") (name "Net-(U2-SW)") (class "Default")
      (node (ref "L2") (pin "1") (pinfunction "1_1") (pintype "passive"))
      (node (ref "U2") (pin "3") (pinfunction "SW_3") (pintype "output"))
    )
    (net (code "87") (name "unconnected-(U1-MDIRN-Pad7)") (class "Default")
      (node (ref "U1") (pin "7") (pinfunction "MDIRN_7") (pintype "bidirectional+no_connect"))
    )
    (net (code "88") (name "unconnected-(U1-MDIRP-Pad8)") (class "Default")
      (node (ref "U1") (pin "8") (pinfunction "MDIRP_8") (pintype "bidirectional+no_connect"))
    )
    (net (code "89") (name "unconnected-(U1-MDITN-Pad9)") (class "Default")
      (node (ref "U1") (pin "9") (pinfunction "MDITN_9") (pintype "bidirectional+no_connect"))
    )
    (net (code "90") (name "unconnected-(U1-MDITP-Pad10)") (class "Default")
      (node (ref "U1") (pin "10") (pinfunction "MDITP_10") (pintype "bidirectional+no_connect"))
    )
    (net (code "91") (name "unconnected-(U1-PA0{slash}ADC0{slash}OP3_O0-Pad21)") (class "Default")
      (node (ref "U1") (pin "21") (pinfunction "PA0/ADC0/OP3_O0_21") (pintype "bidirectional"))
    )
    (net (code "92") (name "unconnected-(U2-NC.-Pad1)") (class "Default")
      (node (ref "U2") (pin "1") (pinfunction "NC._1") (pintype "passive+no_connect"))
    )
  )
)
